# Link232-wifi-c64.net
KiCad netlist of a schematic drawn in EAGLE
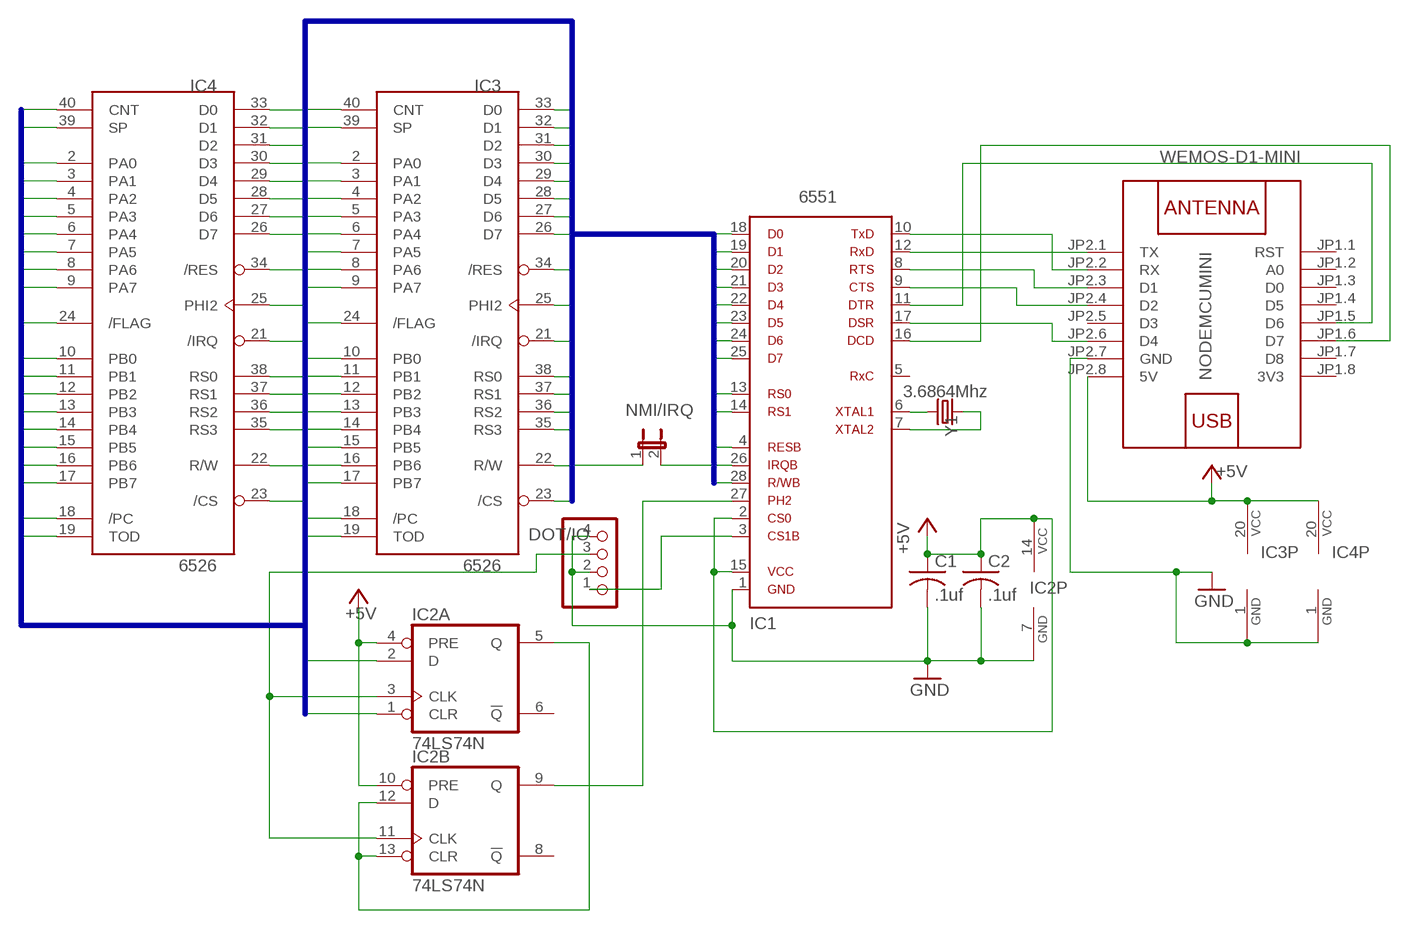
[diagram p0: schematic, sheet 1]

(export (version "E")
  (design (tool "Eeschema 10.0.6"))
  (components
    (comp (ref "C1")
      (value ".1uf")
      (footprint "eagle-import:C050-024X044")
      (libsource (lib "eagle-import") (part "C-US050-024X044"))
    )
    (comp (ref "C2")
      (value ".1uf")
      (footprint "eagle-import:C050-024X044")
      (libsource (lib "eagle-import") (part "C-US050-024X044"))
    )
    (comp (ref "IC1")
      (value "6551")
      (footprint "eagle-import:6551")
      (libsource (lib "eagle-import") (part "6551"))
    )
    (comp (ref "IC2")
      (value "74LS74N")
      (footprint "eagle-import:DIL14")
      (libsource (lib "eagle-import") (part "7474NLS"))
    )
    (comp (ref "IC3")
      (value "6526")
      (footprint "eagle-import:DIP40")
      (libsource (lib "eagle-import") (part "6526"))
    )
    (comp (ref "IC4")
      (value "6526")
      (footprint "eagle-import:DIP40")
      (libsource (lib "eagle-import") (part "6526"))
    )
    (comp (ref "JP1")
      (value "NMI/IRQ")
      (footprint "eagle-import:JP1")
      (libsource (lib "eagle-import") (part "JP1E"))
    )
    (comp (ref "JP2")
      (value "DOT/IO")
      (footprint "eagle-import:1X04")
      (libsource (lib "eagle-import") (part "PINHD-1X4"))
    )
    (comp (ref "NODEMCUMINI")
      (value "WEMOS-D1-MINI")
      (footprint "eagle-import:WEMOS-D1-MINI")
      (libsource (lib "eagle-import") (part "WEMOS-D1-MINI"))
    )
    (comp (ref "Y1")
      (value "3.6864Mhz")
      (footprint "eagle-import:HC49US")
      (libsource (lib "eagle-import") (part "CRYSTALPTH-HC49US"))
    )
  )
  (nets
    (net (code "1") (name "+5V") (class "Default")
      (node (ref "C1") (pin "1") (pinfunction "1_1") (pintype "passive"))
      (node (ref "C2") (pin "1") (pinfunction "1_1") (pintype "passive"))
      (node (ref "IC1") (pin "15") (pinfunction "15_15") (pintype "passive"))
      (node (ref "IC1") (pin "2") (pinfunction "2_2") (pintype "passive"))
      (node (ref "IC2") (pin "10") (pinfunction "PRE_10") (pintype "input"))
      (node (ref "IC2") (pin "14") (pinfunction "VCC_14") (pintype "power_in"))
      (node (ref "IC2") (pin "4") (pinfunction "PRE_4") (pintype "input"))
      (node (ref "IC3") (pin "20") (pinfunction "VCC_20") (pintype "power_in"))
      (node (ref "IC4") (pin "20") (pinfunction "VCC_20") (pintype "power_in"))
      (node (ref "NODEMCUMINI") (pin "JP2.8") (pinfunction "5V_JP2.8") (pintype "power_in"))
    )
    (net (code "2") (name "/3V3") (class "Default")
      (node (ref "NODEMCUMINI") (pin "JP1.8") (pinfunction "3V3_JP1.8") (pintype "power_in"))
    )
    (net (code "3") (name "/CNT") (class "Default")
      (node (ref "IC3") (pin "40") (pinfunction "CNT_40") (pintype "input"))
      (node (ref "IC4") (pin "40") (pinfunction "CNT_40") (pintype "input"))
    )
    (net (code "4") (name "/D0") (class "Default")
      (node (ref "IC1") (pin "18") (pinfunction "18_18") (pintype "passive"))
      (node (ref "IC3") (pin "33") (pinfunction "D0_33") (pintype "bidirectional"))
      (node (ref "IC4") (pin "33") (pinfunction "D0_33") (pintype "bidirectional"))
    )
    (net (code "5") (name "/D1") (class "Default")
      (node (ref "IC1") (pin "19") (pinfunction "19_19") (pintype "passive"))
      (node (ref "IC3") (pin "32") (pinfunction "D1_32") (pintype "bidirectional"))
      (node (ref "IC4") (pin "32") (pinfunction "D1_32") (pintype "bidirectional"))
    )
    (net (code "6") (name "/D2") (class "Default")
      (node (ref "IC1") (pin "20") (pinfunction "20_20") (pintype "passive"))
      (node (ref "IC3") (pin "31") (pinfunction "D2_31") (pintype "bidirectional"))
      (node (ref "IC4") (pin "31") (pinfunction "D2_31") (pintype "bidirectional"))
    )
    (net (code "7") (name "/D3") (class "Default")
      (node (ref "IC1") (pin "21") (pinfunction "21_21") (pintype "passive"))
      (node (ref "IC3") (pin "30") (pinfunction "D3_30") (pintype "bidirectional"))
      (node (ref "IC4") (pin "30") (pinfunction "D3_30") (pintype "bidirectional"))
    )
    (net (code "8") (name "/D4") (class "Default")
      (node (ref "IC1") (pin "22") (pinfunction "22_22") (pintype "passive"))
      (node (ref "IC3") (pin "29") (pinfunction "D4_29") (pintype "bidirectional"))
      (node (ref "IC4") (pin "29") (pinfunction "D4_29") (pintype "bidirectional"))
    )
    (net (code "9") (name "/D5") (class "Default")
      (node (ref "IC1") (pin "23") (pinfunction "23_23") (pintype "passive"))
      (node (ref "IC3") (pin "28") (pinfunction "D5_28") (pintype "bidirectional"))
      (node (ref "IC4") (pin "28") (pinfunction "D5_28") (pintype "bidirectional"))
    )
    (net (code "10") (name "/D6") (class "Default")
      (node (ref "IC1") (pin "24") (pinfunction "24_24") (pintype "passive"))
      (node (ref "IC3") (pin "27") (pinfunction "D6_27") (pintype "bidirectional"))
      (node (ref "IC4") (pin "27") (pinfunction "D6_27") (pintype "bidirectional"))
    )
    (net (code "11") (name "/D7") (class "Default")
      (node (ref "IC1") (pin "25") (pinfunction "25_25") (pintype "passive"))
      (node (ref "IC3") (pin "26") (pinfunction "D7_26") (pintype "bidirectional"))
      (node (ref "IC4") (pin "26") (pinfunction "D7_26") (pintype "bidirectional"))
    )
    (net (code "12") (name "/IRQ") (class "Default")
      (node (ref "IC3") (pin "21") (pinfunction "/IRQ_21") (pintype "open_collector"))
      (node (ref "IC4") (pin "21") (pinfunction "/IRQ_21") (pintype "open_collector"))
      (node (ref "JP1") (pin "1") (pinfunction "1_1") (pintype "passive"))
    )
    (net (code "13") (name "/PA0") (class "Default")
      (node (ref "IC3") (pin "2") (pinfunction "PA0_2") (pintype "bidirectional"))
      (node (ref "IC4") (pin "2") (pinfunction "PA0_2") (pintype "bidirectional"))
    )
    (net (code "14") (name "/PA1") (class "Default")
      (node (ref "IC3") (pin "3") (pinfunction "PA1_3") (pintype "bidirectional"))
      (node (ref "IC4") (pin "3") (pinfunction "PA1_3") (pintype "bidirectional"))
    )
    (net (code "15") (name "/PA2") (class "Default")
      (node (ref "IC3") (pin "4") (pinfunction "PA2_4") (pintype "bidirectional"))
      (node (ref "IC4") (pin "4") (pinfunction "PA2_4") (pintype "bidirectional"))
    )
    (net (code "16") (name "/PA3") (class "Default")
      (node (ref "IC3") (pin "5") (pinfunction "PA3_5") (pintype "bidirectional"))
      (node (ref "IC4") (pin "5") (pinfunction "PA3_5") (pintype "bidirectional"))
    )
    (net (code "17") (name "/PA4") (class "Default")
      (node (ref "IC3") (pin "6") (pinfunction "PA4_6") (pintype "bidirectional"))
      (node (ref "IC4") (pin "6") (pinfunction "PA4_6") (pintype "bidirectional"))
    )
    (net (code "18") (name "/PA5") (class "Default")
      (node (ref "IC3") (pin "7") (pinfunction "PA5_7") (pintype "bidirectional"))
      (node (ref "IC4") (pin "7") (pinfunction "PA5_7") (pintype "bidirectional"))
    )
    (net (code "19") (name "/PA6") (class "Default")
      (node (ref "IC3") (pin "8") (pinfunction "PA6_8") (pintype "bidirectional"))
      (node (ref "IC4") (pin "8") (pinfunction "PA6_8") (pintype "bidirectional"))
    )
    (net (code "20") (name "/PA7") (class "Default")
      (node (ref "IC3") (pin "9") (pinfunction "PA7_9") (pintype "bidirectional"))
      (node (ref "IC4") (pin "9") (pinfunction "PA7_9") (pintype "bidirectional"))
    )
    (net (code "21") (name "/PB0") (class "Default")
      (node (ref "IC3") (pin "10") (pinfunction "PB0_10") (pintype "bidirectional"))
      (node (ref "IC4") (pin "10") (pinfunction "PB0_10") (pintype "bidirectional"))
    )
    (net (code "22") (name "/PB1") (class "Default")
      (node (ref "IC3") (pin "11") (pinfunction "PB1_11") (pintype "bidirectional"))
      (node (ref "IC4") (pin "11") (pinfunction "PB1_11") (pintype "bidirectional"))
    )
    (net (code "23") (name "/PB2") (class "Default")
      (node (ref "IC3") (pin "12") (pinfunction "PB2_12") (pintype "bidirectional"))
      (node (ref "IC4") (pin "12") (pinfunction "PB2_12") (pintype "bidirectional"))
    )
    (net (code "24") (name "/PB3") (class "Default")
      (node (ref "IC3") (pin "13") (pinfunction "PB3_13") (pintype "bidirectional"))
      (node (ref "IC4") (pin "13") (pinfunction "PB3_13") (pintype "bidirectional"))
    )
    (net (code "25") (name "/PB4") (class "Default")
      (node (ref "IC3") (pin "14") (pinfunction "PB4_14") (pintype "bidirectional"))
      (node (ref "IC4") (pin "14") (pinfunction "PB4_14") (pintype "bidirectional"))
    )
    (net (code "26") (name "/PB5") (class "Default")
      (node (ref "IC3") (pin "15") (pinfunction "PB5_15") (pintype "bidirectional"))
      (node (ref "IC4") (pin "15") (pinfunction "PB5_15") (pintype "bidirectional"))
    )
    (net (code "27") (name "/PB6") (class "Default")
      (node (ref "IC3") (pin "16") (pinfunction "PB6_16") (pintype "bidirectional"))
      (node (ref "IC4") (pin "16") (pinfunction "PB6_16") (pintype "bidirectional"))
    )
    (net (code "28") (name "/PB7") (class "Default")
      (node (ref "IC3") (pin "17") (pinfunction "PB7_17") (pintype "bidirectional"))
      (node (ref "IC4") (pin "17") (pinfunction "PB7_17") (pintype "bidirectional"))
    )
    (net (code "29") (name "/PHI2") (class "Default")
      (node (ref "IC2") (pin "1") (pinfunction "CLR_1") (pintype "input"))
      (node (ref "IC2") (pin "2") (pinfunction "D_2") (pintype "input"))
      (node (ref "IC3") (pin "25") (pinfunction "PHI2_25") (pintype "input"))
      (node (ref "IC4") (pin "25") (pinfunction "PHI2_25") (pintype "input"))
    )
    (net (code "30") (name "/RES") (class "Default")
      (node (ref "IC1") (pin "4") (pinfunction "4_4") (pintype "passive"))
      (node (ref "IC3") (pin "34") (pinfunction "/RES_34") (pintype "input"))
      (node (ref "IC4") (pin "34") (pinfunction "/RES_34") (pintype "input"))
    )
    (net (code "31") (name "/RS0") (class "Default")
      (node (ref "IC1") (pin "13") (pinfunction "13_13") (pintype "passive"))
      (node (ref "IC3") (pin "38") (pinfunction "RS0_38") (pintype "input"))
      (node (ref "IC4") (pin "38") (pinfunction "RS0_38") (pintype "input"))
    )
    (net (code "32") (name "/RS1") (class "Default")
      (node (ref "IC1") (pin "14") (pinfunction "14_14") (pintype "passive"))
      (node (ref "IC3") (pin "37") (pinfunction "RS1_37") (pintype "input"))
      (node (ref "IC4") (pin "37") (pinfunction "RS1_37") (pintype "input"))
    )
    (net (code "33") (name "/RS2") (class "Default")
      (node (ref "IC3") (pin "36") (pinfunction "RS2_36") (pintype "input"))
      (node (ref "IC4") (pin "36") (pinfunction "RS2_36") (pintype "input"))
    )
    (net (code "34") (name "/RS3") (class "Default")
      (node (ref "IC3") (pin "35") (pinfunction "RS3_35") (pintype "input"))
      (node (ref "IC4") (pin "35") (pinfunction "RS3_35") (pintype "input"))
    )
    (net (code "35") (name "/RW") (class "Default")
      (node (ref "IC1") (pin "28") (pinfunction "28_28") (pintype "passive"))
      (node (ref "IC3") (pin "22") (pinfunction "R/W_22") (pintype "input"))
      (node (ref "IC4") (pin "22") (pinfunction "R/W_22") (pintype "input"))
    )
    (net (code "36") (name "/SP") (class "Default")
      (node (ref "IC3") (pin "39") (pinfunction "SP_39") (pintype "bidirectional"))
      (node (ref "IC4") (pin "39") (pinfunction "SP_39") (pintype "bidirectional"))
    )
    (net (code "37") (name "/TOD") (class "Default")
      (node (ref "IC3") (pin "19") (pinfunction "TOD_19") (pintype "bidirectional"))
      (node (ref "IC4") (pin "19") (pinfunction "TOD_19") (pintype "bidirectional"))
    )
    (net (code "38") (name "/{slash}CS") (class "Default")
      (node (ref "IC3") (pin "23") (pinfunction "/CS_23") (pintype "input"))
      (node (ref "IC4") (pin "23") (pinfunction "/CS_23") (pintype "input"))
    )
    (net (code "39") (name "/{slash}FLAG") (class "Default")
      (node (ref "IC3") (pin "24") (pinfunction "/FLAG_24") (pintype "input"))
      (node (ref "IC4") (pin "24") (pinfunction "/FLAG_24") (pintype "input"))
    )
    (net (code "40") (name "/{slash}PC") (class "Default")
      (node (ref "IC3") (pin "18") (pinfunction "/PC_18") (pintype "bidirectional"))
      (node (ref "IC4") (pin "18") (pinfunction "/PC_18") (pintype "bidirectional"))
    )
    (net (code "41") (name "GND") (class "Default")
      (node (ref "C1") (pin "2") (pinfunction "2_2") (pintype "passive"))
      (node (ref "C2") (pin "2") (pinfunction "2_2") (pintype "passive"))
      (node (ref "IC1") (pin "1") (pinfunction "1_1") (pintype "passive"))
      (node (ref "IC2") (pin "7") (pinfunction "GND_7") (pintype "power_in"))
      (node (ref "IC3") (pin "1") (pinfunction "GND_1") (pintype "power_in"))
      (node (ref "IC4") (pin "1") (pinfunction "GND_1") (pintype "power_in"))
      (node (ref "JP2") (pin "2") (pinfunction "2_2") (pintype "passive"))
      (node (ref "JP2") (pin "4") (pinfunction "4_4") (pintype "passive"))
      (node (ref "NODEMCUMINI") (pin "JP2.7") (pinfunction "GND_JP2.7") (pintype "power_in"))
    )
    (net (code "42") (name "Net-(IC1-Pad3)") (class "Default")
      (node (ref "IC1") (pin "3") (pinfunction "3_3") (pintype "passive"))
      (node (ref "JP2") (pin "1") (pinfunction "1_1") (pintype "passive"))
    )
    (net (code "43") (name "Net-(IC1-Pad6)") (class "Default")
      (node (ref "IC1") (pin "6") (pinfunction "6_6") (pintype "passive"))
      (node (ref "Y1") (pin "2") (pinfunction "2_2") (pintype "passive"))
    )
    (net (code "44") (name "Net-(IC1-Pad7)") (class "Default")
      (node (ref "IC1") (pin "7") (pinfunction "7_7") (pintype "passive"))
      (node (ref "Y1") (pin "1") (pinfunction "1_1") (pintype "passive"))
    )
    (net (code "45") (name "Net-(IC1-Pad26)") (class "Default")
      (node (ref "IC1") (pin "26") (pinfunction "26_26") (pintype "passive"))
      (node (ref "JP1") (pin "2") (pinfunction "2_2") (pintype "passive"))
    )
    (net (code "46") (name "Net-(IC2A-CLK)") (class "Default")
      (node (ref "IC2") (pin "11") (pinfunction "CLK_11") (pintype "input"))
      (node (ref "IC2") (pin "3") (pinfunction "CLK_3") (pintype "input"))
      (node (ref "JP2") (pin "3") (pinfunction "3_3") (pintype "passive"))
    )
    (net (code "47") (name "Net-(IC2A-Q)") (class "Default")
      (node (ref "IC2") (pin "12") (pinfunction "D_12") (pintype "input"))
      (node (ref "IC2") (pin "13") (pinfunction "CLR_13") (pintype "input"))
      (node (ref "IC2") (pin "5") (pinfunction "Q_5") (pintype "output"))
    )
    (net (code "48") (name "Net-(IC2B-Q)") (class "Default")
      (node (ref "IC1") (pin "27") (pinfunction "27_27") (pintype "passive"))
      (node (ref "IC2") (pin "9") (pinfunction "Q_9") (pintype "output"))
    )
    (net (code "49") (name "Net-(NODEMCUMINI-D1)") (class "Default")
      (node (ref "IC1") (pin "8") (pinfunction "8_8") (pintype "passive"))
      (node (ref "NODEMCUMINI") (pin "JP2.3") (pinfunction "D1_JP2.3") (pintype "bidirectional"))
    )
    (net (code "50") (name "Net-(NODEMCUMINI-D2)") (class "Default")
      (node (ref "IC1") (pin "9") (pinfunction "9_9") (pintype "passive"))
      (node (ref "NODEMCUMINI") (pin "JP2.4") (pinfunction "D2_JP2.4") (pintype "bidirectional"))
    )
    (net (code "51") (name "Net-(NODEMCUMINI-D4)") (class "Default")
      (node (ref "IC1") (pin "17") (pinfunction "17_17") (pintype "passive"))
      (node (ref "NODEMCUMINI") (pin "JP2.6") (pinfunction "D4_JP2.6") (pintype "bidirectional"))
    )
    (net (code "52") (name "Net-(NODEMCUMINI-D6)") (class "Default")
      (node (ref "IC1") (pin "11") (pinfunction "11_11") (pintype "passive"))
      (node (ref "NODEMCUMINI") (pin "JP1.5") (pinfunction "D6_JP1.5") (pintype "bidirectional"))
    )
    (net (code "53") (name "Net-(NODEMCUMINI-D7)") (class "Default")
      (node (ref "IC1") (pin "16") (pinfunction "16_16") (pintype "passive"))
      (node (ref "NODEMCUMINI") (pin "JP1.6") (pinfunction "D7_JP1.6") (pintype "bidirectional"))
    )
    (net (code "54") (name "Net-(NODEMCUMINI-RX)") (class "Default")
      (node (ref "IC1") (pin "10") (pinfunction "10_10") (pintype "passive"))
      (node (ref "NODEMCUMINI") (pin "JP2.2") (pinfunction "RX_JP2.2") (pintype "bidirectional"))
    )
    (net (code "55") (name "Net-(NODEMCUMINI-TX)") (class "Default")
      (node (ref "IC1") (pin "12") (pinfunction "12_12") (pintype "passive"))
      (node (ref "NODEMCUMINI") (pin "JP2.1") (pinfunction "TX_JP2.1") (pintype "bidirectional"))
    )
    (net (code "56") (name "unconnected-(IC1-Pad5)") (class "Default")
      (node (ref "IC1") (pin "5") (pinfunction "5_5") (pintype "passive"))
    )
    (net (code "57") (name "unconnected-(IC2A-~{Q}-Pad6)") (class "Default")
      (node (ref "IC2") (pin "6") (pinfunction "~{Q}_6") (pintype "output"))
    )
    (net (code "58") (name "unconnected-(IC2B-~{Q}-Pad8)") (class "Default")
      (node (ref "IC2") (pin "8") (pinfunction "~{Q}_8") (pintype "output"))
    )
    (net (code "59") (name "unconnected-(NODEMCUMINI-A0-PadJP1.2)") (class "Default")
      (node (ref "NODEMCUMINI") (pin "JP1.2") (pinfunction "A0_JP1.2") (pintype "bidirectional"))
    )
    (net (code "60") (name "unconnected-(NODEMCUMINI-D0-PadJP1.3)") (class "Default")
      (node (ref "NODEMCUMINI") (pin "JP1.3") (pinfunction "D0_JP1.3") (pintype "bidirectional"))
    )
    (net (code "61") (name "unconnected-(NODEMCUMINI-D3-PadJP2.5)") (class "Default")
      (node (ref "NODEMCUMINI") (pin "JP2.5") (pinfunction "D3_JP2.5") (pintype "bidirectional"))
    )
    (net (code "62") (name "unconnected-(NODEMCUMINI-D5-PadJP1.4)") (class "Default")
      (node (ref "NODEMCUMINI") (pin "JP1.4") (pinfunction "D5_JP1.4") (pintype "bidirectional"))
    )
    (net (code "63") (name "unconnected-(NODEMCUMINI-D8-PadJP1.7)") (class "Default")
      (node (ref "NODEMCUMINI") (pin "JP1.7") (pinfunction "D8_JP1.7") (pintype "bidirectional"))
    )
    (net (code "64") (name "unconnected-(NODEMCUMINI-RST-PadJP1.1)") (class "Default")
      (node (ref "NODEMCUMINI") (pin "JP1.1") (pinfunction "RST_JP1.1") (pintype "bidirectional"))
    )
  )
)
